# C3427-1.net
KiCad netlist of a schematic drawn in EAGLE
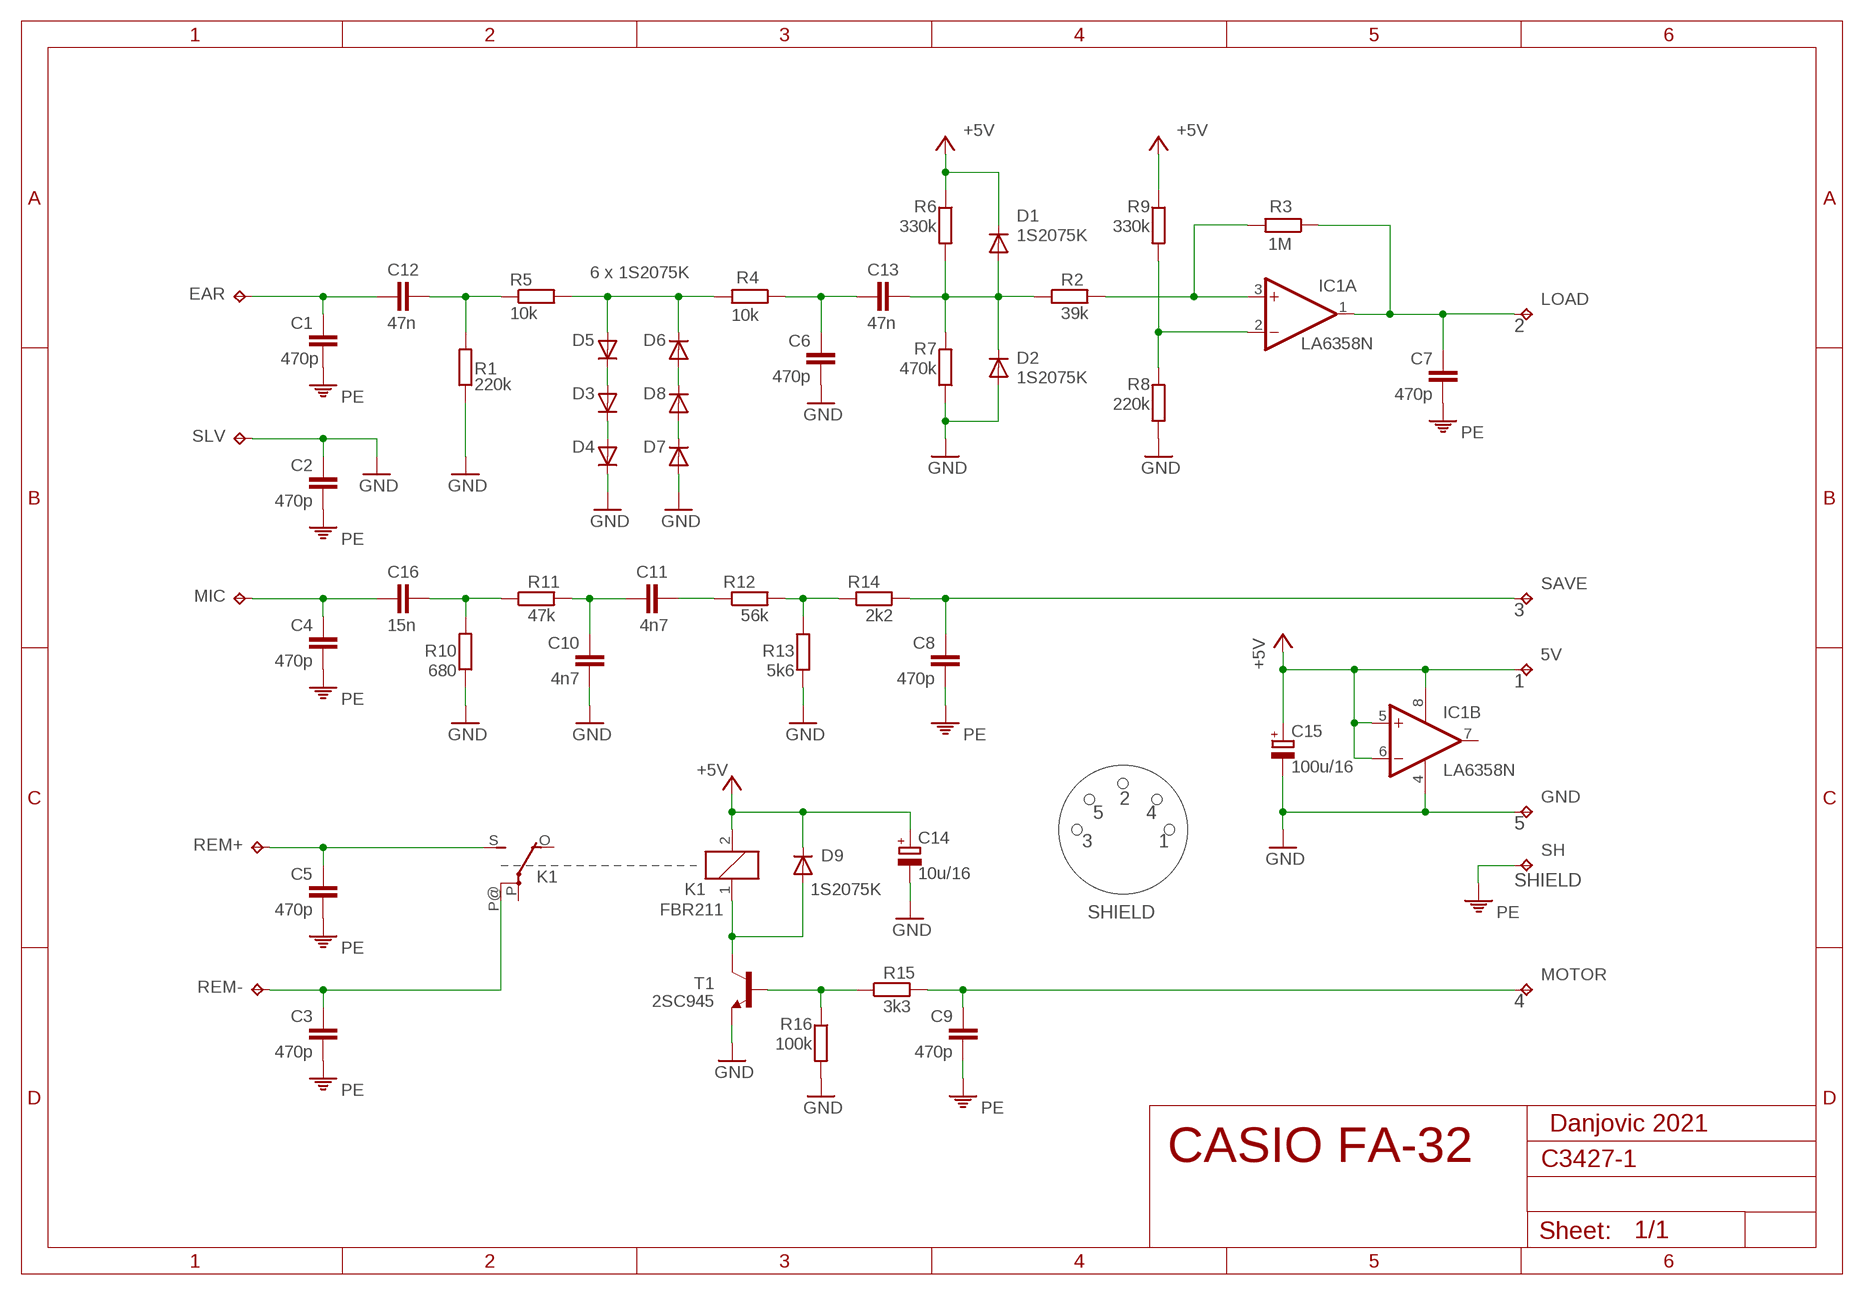
[diagram p0: schematic, sheet 1]

(export (version "E")
  (design (tool "Eeschema 10.0.6"))
  (components
    (comp (ref "5V")
      (value "TPPAD1-13")
      (footprint "eagle-import:P1-13")
      (libsource (lib "eagle-import") (part "TPPAD1-13"))
    )
    (comp (ref "C1")
      (value "470p")
      (footprint "eagle-import:C050-024X044")
      (libsource (lib "eagle-import") (part "C-EU050-024X044"))
    )
    (comp (ref "C2")
      (value "470p")
      (footprint "eagle-import:C050-024X044")
      (libsource (lib "eagle-import") (part "C-EU050-024X044"))
    )
    (comp (ref "C3")
      (value "470p")
      (footprint "eagle-import:C050-024X044")
      (libsource (lib "eagle-import") (part "C-EU050-024X044"))
    )
    (comp (ref "C4")
      (value "470p")
      (footprint "eagle-import:C050-024X044")
      (libsource (lib "eagle-import") (part "C-EU050-024X044"))
    )
    (comp (ref "C5")
      (value "470p")
      (footprint "eagle-import:C050-024X044")
      (libsource (lib "eagle-import") (part "C-EU050-024X044"))
    )
    (comp (ref "C6")
      (value "470p")
      (footprint "eagle-import:C050-024X044")
      (libsource (lib "eagle-import") (part "C-EU050-024X044"))
    )
    (comp (ref "C7")
      (value "470p")
      (footprint "eagle-import:C050-024X044")
      (libsource (lib "eagle-import") (part "C-EU050-024X044"))
    )
    (comp (ref "C8")
      (value "470p")
      (footprint "eagle-import:C050-024X044")
      (libsource (lib "eagle-import") (part "C-EU050-024X044"))
    )
    (comp (ref "C9")
      (value "470p")
      (footprint "eagle-import:C050-024X044")
      (libsource (lib "eagle-import") (part "C-EU050-024X044"))
    )
    (comp (ref "C10")
      (value "4n7")
      (footprint "eagle-import:C050-024X044")
      (libsource (lib "eagle-import") (part "C-EU050-024X044"))
    )
    (comp (ref "C11")
      (value "4n7")
      (footprint "eagle-import:C050-024X044")
      (libsource (lib "eagle-import") (part "C-EU050-024X044"))
    )
    (comp (ref "C12")
      (value "47n")
      (footprint "eagle-import:C050-045X075")
      (libsource (lib "eagle-import") (part "C-EU050-045X075"))
    )
    (comp (ref "C13")
      (value "47n")
      (footprint "eagle-import:C050-045X075")
      (libsource (lib "eagle-import") (part "C-EU050-045X075"))
    )
    (comp (ref "C14")
      (value "10u/16")
      (footprint "eagle-import:E2-4")
      (libsource (lib "eagle-import") (part "CPOL-EUE2-4"))
    )
    (comp (ref "C15")
      (value "100u/16")
      (footprint "eagle-import:E2,5-6")
      (libsource (lib "eagle-import") (part "CPOL-EUE2.5-6"))
    )
    (comp (ref "C16")
      (value "15n")
      (footprint "eagle-import:C050-024X044")
      (libsource (lib "eagle-import") (part "C-EU050-024X044"))
    )
    (comp (ref "D1")
      (value "1S2075K")
      (footprint "eagle-import:D-7.5")
      (libsource (lib "eagle-import") (part "DIODE-D-7.5"))
    )
    (comp (ref "D2")
      (value "1S2075K")
      (footprint "eagle-import:D-7.5")
      (libsource (lib "eagle-import") (part "DIODE-D-7.5"))
    )
    (comp (ref "D3")
      (value "1S2075K")
      (footprint "eagle-import:D-7.5")
      (libsource (lib "eagle-import") (part "DIODE-D-7.5"))
    )
    (comp (ref "D4")
      (value "1S2075K")
      (footprint "eagle-import:D-7.5")
      (libsource (lib "eagle-import") (part "DIODE-D-7.5"))
    )
    (comp (ref "D5")
      (value "1S2075K")
      (footprint "eagle-import:D-7.5")
      (libsource (lib "eagle-import") (part "DIODE-D-7.5"))
    )
    (comp (ref "D6")
      (value "1S2075K")
      (footprint "eagle-import:D-7.5")
      (libsource (lib "eagle-import") (part "DIODE-D-7.5"))
    )
    (comp (ref "D7")
      (value "1S2075K")
      (footprint "eagle-import:D-7.5")
      (libsource (lib "eagle-import") (part "DIODE-D-7.5"))
    )
    (comp (ref "D8")
      (value "1S2075K")
      (footprint "eagle-import:D-7.5")
      (libsource (lib "eagle-import") (part "DIODE-D-7.5"))
    )
    (comp (ref "D9")
      (value "1S2075K")
      (footprint "eagle-import:D-7.5")
      (libsource (lib "eagle-import") (part "DIODE-D-7.5"))
    )
    (comp (ref "EAR")
      (value "TPPAD1-13")
      (footprint "eagle-import:P1-13")
      (libsource (lib "eagle-import") (part "TPPAD1-13"))
    )
    (comp (ref "GND")
      (value "TPPAD1-13")
      (footprint "eagle-import:P1-13")
      (libsource (lib "eagle-import") (part "TPPAD1-13"))
    )
    (comp (ref "IC1")
      (value "LA6358N")
      (footprint "eagle-import:DIL08")
      (libsource (lib "eagle-import") (part "LM358N"))
    )
    (comp (ref "K1")
      (value "FBR211")
      (footprint "eagle-import:FRS1B")
      (libsource (lib "eagle-import") (part "FRS1B"))
    )
    (comp (ref "LOAD")
      (value "TPPAD1-13")
      (footprint "eagle-import:P1-13")
      (libsource (lib "eagle-import") (part "TPPAD1-13"))
    )
    (comp (ref "MIC")
      (value "TPPAD1-13")
      (footprint "eagle-import:P1-13")
      (libsource (lib "eagle-import") (part "TPPAD1-13"))
    )
    (comp (ref "MOTOR")
      (value "TPPAD1-13")
      (footprint "eagle-import:P1-13")
      (libsource (lib "eagle-import") (part "TPPAD1-13"))
    )
    (comp (ref "R1")
      (value "220k")
      (footprint "eagle-import:0204_7")
      (libsource (lib "eagle-import") (part "R-EU_0204/7"))
    )
    (comp (ref "R2")
      (value "39k")
      (footprint "eagle-import:0204_7")
      (libsource (lib "eagle-import") (part "R-EU_0204/7"))
    )
    (comp (ref "R3")
      (value "1M")
      (footprint "eagle-import:0204_7")
      (libsource (lib "eagle-import") (part "R-EU_0204/7"))
    )
    (comp (ref "R4")
      (value "10k")
      (footprint "eagle-import:0204_7")
      (libsource (lib "eagle-import") (part "R-EU_0204/7"))
    )
    (comp (ref "R5")
      (value "10k")
      (footprint "eagle-import:0204_7")
      (libsource (lib "eagle-import") (part "R-EU_0204/7"))
    )
    (comp (ref "R6")
      (value "330k")
      (footprint "eagle-import:0204_7")
      (libsource (lib "eagle-import") (part "R-EU_0204/7"))
    )
    (comp (ref "R7")
      (value "470k")
      (footprint "eagle-import:0204_7")
      (libsource (lib "eagle-import") (part "R-EU_0204/7"))
    )
    (comp (ref "R8")
      (value "220k")
      (footprint "eagle-import:0204_7")
      (libsource (lib "eagle-import") (part "R-EU_0204/7"))
    )
    (comp (ref "R9")
      (value "330k")
      (footprint "eagle-import:0204_7")
      (libsource (lib "eagle-import") (part "R-EU_0204/7"))
    )
    (comp (ref "R10")
      (value "680")
      (footprint "eagle-import:0204_7")
      (libsource (lib "eagle-import") (part "R-EU_0204/7"))
    )
    (comp (ref "R11")
      (value "47k")
      (footprint "eagle-import:0204_7")
      (libsource (lib "eagle-import") (part "R-EU_0204/7"))
    )
    (comp (ref "R12")
      (value "56k")
      (footprint "eagle-import:0204_7")
      (libsource (lib "eagle-import") (part "R-EU_0204/7"))
    )
    (comp (ref "R13")
      (value "5k6")
      (footprint "eagle-import:0204_7")
      (libsource (lib "eagle-import") (part "R-EU_0204/7"))
    )
    (comp (ref "R14")
      (value "2k2")
      (footprint "eagle-import:0204_7")
      (libsource (lib "eagle-import") (part "R-EU_0204/7"))
    )
    (comp (ref "R15")
      (value "3k3")
      (footprint "eagle-import:0204_7")
      (libsource (lib "eagle-import") (part "R-EU_0204/7"))
    )
    (comp (ref "R16")
      (value "100k")
      (footprint "eagle-import:0204_7")
      (libsource (lib "eagle-import") (part "R-EU_0204/7"))
    )
    (comp (ref "REM+")
      (value "TPPAD1-13")
      (footprint "eagle-import:P1-13")
      (libsource (lib "eagle-import") (part "TPPAD1-13"))
    )
    (comp (ref "REM-")
      (value "TPPAD1-13")
      (footprint "eagle-import:P1-13")
      (libsource (lib "eagle-import") (part "TPPAD1-13"))
    )
    (comp (ref "SAVE")
      (value "TPPAD1-13")
      (footprint "eagle-import:P1-13")
      (libsource (lib "eagle-import") (part "TPPAD1-13"))
    )
    (comp (ref "SH")
      (value "TPPAD1-13")
      (footprint "eagle-import:P1-13")
      (libsource (lib "eagle-import") (part "TPPAD1-13"))
    )
    (comp (ref "SLV")
      (value "TPPAD1-13")
      (footprint "eagle-import:P1-13")
      (libsource (lib "eagle-import") (part "TPPAD1-13"))
    )
    (comp (ref "T1")
      (value "2SC945")
      (footprint "eagle-import:TO92-ECB")
      (libsource (lib "eagle-import") (part "2SC945"))
    )
  )
  (nets
    (net (code "1") (name "+5V") (class "Default")
      (node (ref "5V") (pin "TP") (pinfunction "TP_TP") (pintype "input"))
      (node (ref "C14") (pin "+") (pinfunction "+_+") (pintype "passive"))
      (node (ref "C15") (pin "+") (pinfunction "+_+") (pintype "passive"))
      (node (ref "D1") (pin "C") (pinfunction "C_C") (pintype "passive"))
      (node (ref "D9") (pin "C") (pinfunction "C_C") (pintype "passive"))
      (node (ref "IC1") (pin "5") (pinfunction "+IN_5") (pintype "input"))
      (node (ref "IC1") (pin "6") (pinfunction "-IN_6") (pintype "input"))
      (node (ref "IC1") (pin "8") (pinfunction "V+_8") (pintype "power_in"))
      (node (ref "K1") (pin "2") (pinfunction "2_2") (pintype "passive"))
      (node (ref "R6") (pin "1") (pinfunction "1_1") (pintype "passive"))
      (node (ref "R9") (pin "1") (pinfunction "1_1") (pintype "passive"))
    )
    (net (code "2") (name "GND") (class "Default")
      (node (ref "C10") (pin "1") (pinfunction "1_1") (pintype "passive"))
      (node (ref "C14") (pin "-") (pinfunction "-_-") (pintype "passive"))
      (node (ref "C15") (pin "-") (pinfunction "-_-") (pintype "passive"))
      (node (ref "C2") (pin "2") (pinfunction "2_2") (pintype "passive"))
      (node (ref "C6") (pin "1") (pinfunction "1_1") (pintype "passive"))
      (node (ref "D2") (pin "A") (pinfunction "A_A") (pintype "passive"))
      (node (ref "D4") (pin "C") (pinfunction "C_C") (pintype "passive"))
      (node (ref "D7") (pin "A") (pinfunction "A_A") (pintype "passive"))
      (node (ref "GND") (pin "TP") (pinfunction "TP_TP") (pintype "input"))
      (node (ref "IC1") (pin "4") (pinfunction "V-_4") (pintype "power_in"))
      (node (ref "R1") (pin "1") (pinfunction "1_1") (pintype "passive"))
      (node (ref "R10") (pin "1") (pinfunction "1_1") (pintype "passive"))
      (node (ref "R13") (pin "2") (pinfunction "2_2") (pintype "passive"))
      (node (ref "R16") (pin "2") (pinfunction "2_2") (pintype "passive"))
      (node (ref "R7") (pin "1") (pinfunction "1_1") (pintype "passive"))
      (node (ref "R8") (pin "1") (pinfunction "1_1") (pintype "passive"))
      (node (ref "SLV") (pin "TP") (pinfunction "TP_TP") (pintype "input"))
      (node (ref "T1") (pin "E") (pinfunction "E_E") (pintype "passive"))
    )
    (net (code "3") (name "Net-(C1-Pad2)") (class "Default")
      (node (ref "C1") (pin "2") (pinfunction "2_2") (pintype "passive"))
      (node (ref "C12") (pin "2") (pinfunction "2_2") (pintype "passive"))
      (node (ref "EAR") (pin "TP") (pinfunction "TP_TP") (pintype "input"))
    )
    (net (code "4") (name "Net-(C3-Pad2)") (class "Default")
      (node (ref "C3") (pin "2") (pinfunction "2_2") (pintype "passive"))
      (node (ref "K1") (pin "P@") (pinfunction "P_P@") (pintype "passive"))
      (node (ref "REM-") (pin "TP") (pinfunction "TP_TP") (pintype "input"))
    )
    (net (code "5") (name "Net-(C5-Pad2)") (class "Default")
      (node (ref "C5") (pin "2") (pinfunction "2_2") (pintype "passive"))
      (node (ref "K1") (pin "S") (pinfunction "S_S") (pintype "passive"))
      (node (ref "REM+") (pin "TP") (pinfunction "TP_TP") (pintype "input"))
    )
    (net (code "6") (name "Net-(C8-Pad2)") (class "Default")
      (node (ref "C8") (pin "2") (pinfunction "2_2") (pintype "passive"))
      (node (ref "R14") (pin "2") (pinfunction "2_2") (pintype "passive"))
      (node (ref "SAVE") (pin "TP") (pinfunction "TP_TP") (pintype "input"))
    )
    (net (code "7") (name "Net-(C9-Pad2)") (class "Default")
      (node (ref "C9") (pin "2") (pinfunction "2_2") (pintype "passive"))
      (node (ref "MOTOR") (pin "TP") (pinfunction "TP_TP") (pintype "input"))
      (node (ref "R15") (pin "2") (pinfunction "2_2") (pintype "passive"))
    )
    (net (code "8") (name "Net-(C10-Pad2)") (class "Default")
      (node (ref "C10") (pin "2") (pinfunction "2_2") (pintype "passive"))
      (node (ref "C11") (pin "1") (pinfunction "1_1") (pintype "passive"))
      (node (ref "R11") (pin "2") (pinfunction "2_2") (pintype "passive"))
    )
    (net (code "9") (name "Net-(C11-Pad2)") (class "Default")
      (node (ref "C11") (pin "2") (pinfunction "2_2") (pintype "passive"))
      (node (ref "R12") (pin "1") (pinfunction "1_1") (pintype "passive"))
    )
    (net (code "10") (name "Net-(C12-Pad1)") (class "Default")
      (node (ref "C12") (pin "1") (pinfunction "1_1") (pintype "passive"))
      (node (ref "R1") (pin "2") (pinfunction "2_2") (pintype "passive"))
      (node (ref "R5") (pin "1") (pinfunction "1_1") (pintype "passive"))
    )
    (net (code "11") (name "Net-(C13-Pad1)") (class "Default")
      (node (ref "C13") (pin "1") (pinfunction "1_1") (pintype "passive"))
      (node (ref "D1") (pin "A") (pinfunction "A_A") (pintype "passive"))
      (node (ref "D2") (pin "C") (pinfunction "C_C") (pintype "passive"))
      (node (ref "R2") (pin "1") (pinfunction "1_1") (pintype "passive"))
      (node (ref "R6") (pin "2") (pinfunction "2_2") (pintype "passive"))
      (node (ref "R7") (pin "2") (pinfunction "2_2") (pintype "passive"))
    )
    (net (code "12") (name "Net-(C13-Pad2)") (class "Default")
      (node (ref "C13") (pin "2") (pinfunction "2_2") (pintype "passive"))
      (node (ref "C6") (pin "2") (pinfunction "2_2") (pintype "passive"))
      (node (ref "R4") (pin "1") (pinfunction "1_1") (pintype "passive"))
    )
    (net (code "13") (name "Net-(C16-Pad1)") (class "Default")
      (node (ref "C16") (pin "1") (pinfunction "1_1") (pintype "passive"))
      (node (ref "R10") (pin "2") (pinfunction "2_2") (pintype "passive"))
      (node (ref "R11") (pin "1") (pinfunction "1_1") (pintype "passive"))
    )
    (net (code "14") (name "Net-(C16-Pad2)") (class "Default")
      (node (ref "C16") (pin "2") (pinfunction "2_2") (pintype "passive"))
      (node (ref "C4") (pin "2") (pinfunction "2_2") (pintype "passive"))
      (node (ref "MIC") (pin "TP") (pinfunction "TP_TP") (pintype "input"))
    )
    (net (code "15") (name "Net-(D3-PadA)") (class "Default")
      (node (ref "D3") (pin "A") (pinfunction "A_A") (pintype "passive"))
      (node (ref "D5") (pin "C") (pinfunction "C_C") (pintype "passive"))
    )
    (net (code "16") (name "Net-(D3-PadC)") (class "Default")
      (node (ref "D3") (pin "C") (pinfunction "C_C") (pintype "passive"))
      (node (ref "D4") (pin "A") (pinfunction "A_A") (pintype "passive"))
    )
    (net (code "17") (name "Net-(D5-PadA)") (class "Default")
      (node (ref "D5") (pin "A") (pinfunction "A_A") (pintype "passive"))
      (node (ref "D6") (pin "C") (pinfunction "C_C") (pintype "passive"))
      (node (ref "R4") (pin "2") (pinfunction "2_2") (pintype "passive"))
      (node (ref "R5") (pin "2") (pinfunction "2_2") (pintype "passive"))
    )
    (net (code "18") (name "Net-(D6-PadA)") (class "Default")
      (node (ref "D6") (pin "A") (pinfunction "A_A") (pintype "passive"))
      (node (ref "D8") (pin "C") (pinfunction "C_C") (pintype "passive"))
    )
    (net (code "19") (name "Net-(D7-PadC)") (class "Default")
      (node (ref "D7") (pin "C") (pinfunction "C_C") (pintype "passive"))
      (node (ref "D8") (pin "A") (pinfunction "A_A") (pintype "passive"))
    )
    (net (code "20") (name "Net-(D9-PadA)") (class "Default")
      (node (ref "D9") (pin "A") (pinfunction "A_A") (pintype "passive"))
      (node (ref "K1") (pin "1") (pinfunction "1_1") (pintype "passive"))
      (node (ref "T1") (pin "C") (pinfunction "C_C") (pintype "passive"))
    )
    (net (code "21") (name "Net-(IC1A-+IN)") (class "Default")
      (node (ref "IC1") (pin "3") (pinfunction "+IN_3") (pintype "input"))
      (node (ref "R2") (pin "2") (pinfunction "2_2") (pintype "passive"))
      (node (ref "R3") (pin "2") (pinfunction "2_2") (pintype "passive"))
    )
    (net (code "22") (name "Net-(IC1A--IN)") (class "Default")
      (node (ref "IC1") (pin "2") (pinfunction "-IN_2") (pintype "input"))
      (node (ref "R8") (pin "2") (pinfunction "2_2") (pintype "passive"))
      (node (ref "R9") (pin "2") (pinfunction "2_2") (pintype "passive"))
    )
    (net (code "23") (name "Net-(IC1A-OUT)") (class "Default")
      (node (ref "C7") (pin "2") (pinfunction "2_2") (pintype "passive"))
      (node (ref "IC1") (pin "1") (pinfunction "OUT_1") (pintype "output"))
      (node (ref "LOAD") (pin "TP") (pinfunction "TP_TP") (pintype "input"))
      (node (ref "R3") (pin "1") (pinfunction "1_1") (pintype "passive"))
    )
    (net (code "24") (name "Net-(R12-Pad2)") (class "Default")
      (node (ref "R12") (pin "2") (pinfunction "2_2") (pintype "passive"))
      (node (ref "R13") (pin "1") (pinfunction "1_1") (pintype "passive"))
      (node (ref "R14") (pin "1") (pinfunction "1_1") (pintype "passive"))
    )
    (net (code "25") (name "Net-(R15-Pad1)") (class "Default")
      (node (ref "R15") (pin "1") (pinfunction "1_1") (pintype "passive"))
      (node (ref "R16") (pin "1") (pinfunction "1_1") (pintype "passive"))
      (node (ref "T1") (pin "B") (pinfunction "B_B") (pintype "passive"))
    )
    (net (code "26") (name "PE") (class "Default")
      (node (ref "C1") (pin "1") (pinfunction "1_1") (pintype "passive"))
      (node (ref "C2") (pin "1") (pinfunction "1_1") (pintype "passive"))
      (node (ref "C3") (pin "1") (pinfunction "1_1") (pintype "passive"))
      (node (ref "C4") (pin "1") (pinfunction "1_1") (pintype "passive"))
      (node (ref "C5") (pin "1") (pinfunction "1_1") (pintype "passive"))
      (node (ref "C7") (pin "1") (pinfunction "1_1") (pintype "passive"))
      (node (ref "C8") (pin "1") (pinfunction "1_1") (pintype "passive"))
      (node (ref "C9") (pin "1") (pinfunction "1_1") (pintype "passive"))
      (node (ref "SH") (pin "TP") (pinfunction "TP_TP") (pintype "input"))
    )
    (net (code "27") (name "unconnected-(IC1B-OUT-Pad7)") (class "Default")
      (node (ref "IC1") (pin "7") (pinfunction "OUT_7") (pintype "output"))
    )
    (net (code "28") (name "unconnected-(K1-PadO)") (class "Default")
      (node (ref "K1") (pin "O") (pinfunction "O_O") (pintype "passive"))
    )
    (net (code "29") (name "unconnected-(K1-PadP)") (class "Default")
      (node (ref "K1") (pin "P") (pinfunction "P_P") (pintype "passive"))
    )
  )
)
